# E17-04-PRECHARGE-DISCHARGE.net
KiCad netlist of a schematic drawn in Altium Designer
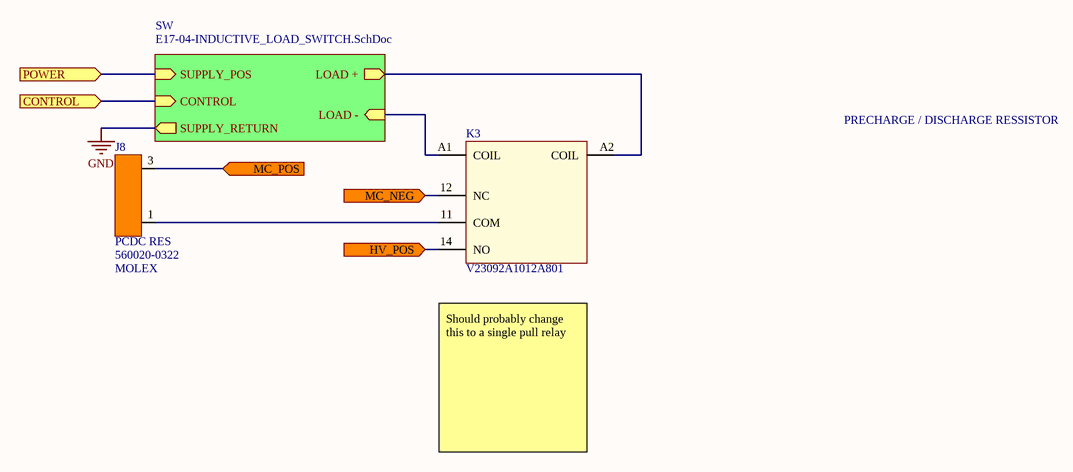
[diagram p0: E17-04-PRECHARGE-DISCHARGE.SchDoc]

(export (version "E")
  (design (tool "Eeschema 10.0.6"))
  (components
    (comp (ref "J8")
      (value "PCDC RES")
      (footprint "MOLEX_DURACLIK_3 RED - VERT  HV")
      (description "MOLEX DURACLIK 3-PIN VERT RED HV")
      (fields
        (field (name "VOLTAGE") "250")
        (field (name "MPN") "560020-0322")
        (field (name "MANUFACTURER") "MOLEX")
      )
      (libsource (lib "Molex_DuraClik") (part "560020-0322_HV"))
    )
    (comp (ref "K3")
      (value "V23092A1012A801")
      (footprint "SCHRACK")
      (description "12V slim SPDT Relay")
      (fields (field (name "MFG") "TE") (field (name "MFG_PN") "V23092A1012A801"))
      (libsource (lib "Relays") (part "V23092A1012A801"))
    )
  )
  (nets
    (net (code "2") (name "/HV_POS") (class "Default")
      (node (ref "K3") (pin "14") (pinfunction "NO_14") (pintype "passive"))
    )
    (net (code "3") (name "/LOAD +") (class "Default")
      (node (ref "K3") (pin "A2") (pinfunction "COIL_A2") (pintype "passive"))
    )
    (net (code "4") (name "/LOAD -") (class "Default")
      (node (ref "K3") (pin "A1") (pinfunction "COIL_A1") (pintype "passive"))
    )
    (net (code "5") (name "/MC_NEG") (class "Default")
      (node (ref "K3") (pin "12") (pinfunction "NC_12") (pintype "passive"))
    )
    (net (code "6") (name "/MC_POS") (class "Default")
      (node (ref "J8") (pin "3") (pinfunction "3_3") (pintype "passive"))
    )
    (net (code "9") (name "Net-(K3-COM)") (class "Default")
      (node (ref "J8") (pin "1") (pinfunction "1_1") (pintype "passive"))
      (node (ref "K3") (pin "11") (pinfunction "COM_11") (pintype "passive"))
    )
  )
)
